# PowerConversion12-5.net
KiCad netlist of a schematic drawn in Altium Designer
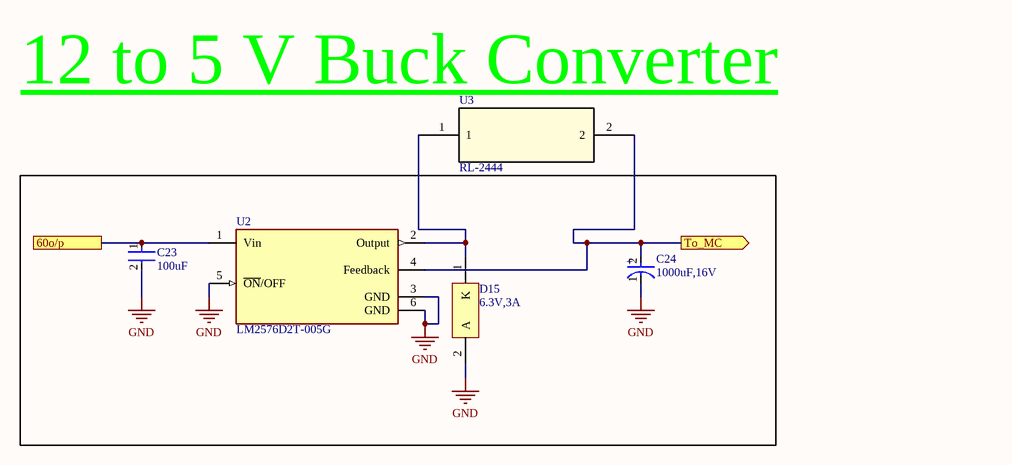
[diagram p0: PowerConversion12-5.SchDoc]

(export (version "E")
  (design (tool "Eeschema 10.0.6"))
  (components
    (comp (ref "C23")
      (value "100uF")
      (footprint "FP-GRM32-0_3-MFG")
      (description "CAP CER 100UF 6.3V X5R 1210")
      (fields
        (field (name "OCTOPART") "https://octopart.com/grm32er60j107me20l-murata-197007")
        (field (name "3DS PART NUMBER") "220-00002")
      )
      (libsource (lib "Altium Content Vault") (part "11868f565c42a9108669ba33697ecf6"))
    )
    (comp (ref "C24")
      (value "1000uF,16V")
      (footprint "FP-FTG-MFG")
      (description "CAP ALUM 1000UF 20% 16V SMD")
      (fields (field (name "TOLERANCE") "20%") (field (name "VOLTAGE") "16V"))
      (libsource (lib "Altium Content Vault") (part "a00bbbee19879c290e62620ae7e47b1"))
    )
    (comp (ref "D15")
      (value "6.3V,3A")
      (footprint "ONSC-AXIAL_LEAD-2-267-05_V")
      (description "Rectifier, 2-Pin Axial_Lead, Pb-Free, Tape and Reel")
      (fields (field (name "PARTNUMBER") "1N5820RLG") (field (name "MANUFACTURER") "On Semiconductor"))
      (libsource (lib "Altium Content Vault") (part "ONSC-D-K1A2-2_A"))
    )
    (comp (ref "U2")
      (value "LM2576D2T-005G")
      (footprint "FP-936A-02-MFG")
      (description "IC REG MULTI CONFG 5V 3A D2PAK-5")
      (fields
        (field (name "MANUFACTURER") "ON Semiconductor")
        (field (name "OCTOPART") "https://octopart.com/lm2576d2t-005g-on+semiconductor-725168")
      )
      (libsource (lib "Altium Content Vault") (part "c423ec427ffa15a9162ce552835b611"))
    )
    (comp (ref "U3")
      (value "RL-2444")
      (footprint "TO_2444_RCE")
      (description "No Description Available")
      (libsource (lib "RL-2444") (part "RL-2444"))
    )
  )
  (nets
    (net (code "1") (name "/60o{slash}p") (class "Default")
      (node (ref "C23") (pin "1") (pinfunction "1_1") (pintype "passive"))
      (node (ref "U2") (pin "1") (pinfunction "Vin_1") (pintype "power_in"))
    )
    (net (code "2") (name "/To_MC") (class "Default")
      (node (ref "C24") (pin "2") (pinfunction "A_2") (pintype "passive"))
      (node (ref "U2") (pin "4") (pinfunction "Feedback_4") (pintype "passive"))
      (node (ref "U3") (pin "2") (pinfunction "2_2") (pintype "passive"))
    )
    (net (code "3") (name "GND") (class "Default")
      (node (ref "C23") (pin "2") (pinfunction "2_2") (pintype "passive"))
      (node (ref "C24") (pin "1") (pinfunction "C_1") (pintype "passive"))
      (node (ref "D15") (pin "2") (pinfunction "A_2") (pintype "passive"))
      (node (ref "U2") (pin "3") (pinfunction "GND_3") (pintype "power_in"))
      (node (ref "U2") (pin "5") (pinfunction "~{ON}/OFF_5") (pintype "input"))
      (node (ref "U2") (pin "6") (pinfunction "GND_6") (pintype "power_in"))
    )
    (net (code "4") (name "Net-(D15-K)") (class "Default")
      (node (ref "D15") (pin "1") (pinfunction "K_1") (pintype "passive"))
      (node (ref "U2") (pin "2") (pinfunction "Output_2") (pintype "output"))
      (node (ref "U3") (pin "1") (pinfunction "1_1") (pintype "passive"))
    )
  )
)
